# Sheet1.net
KiCad netlist of a schematic drawn in Altium Designer
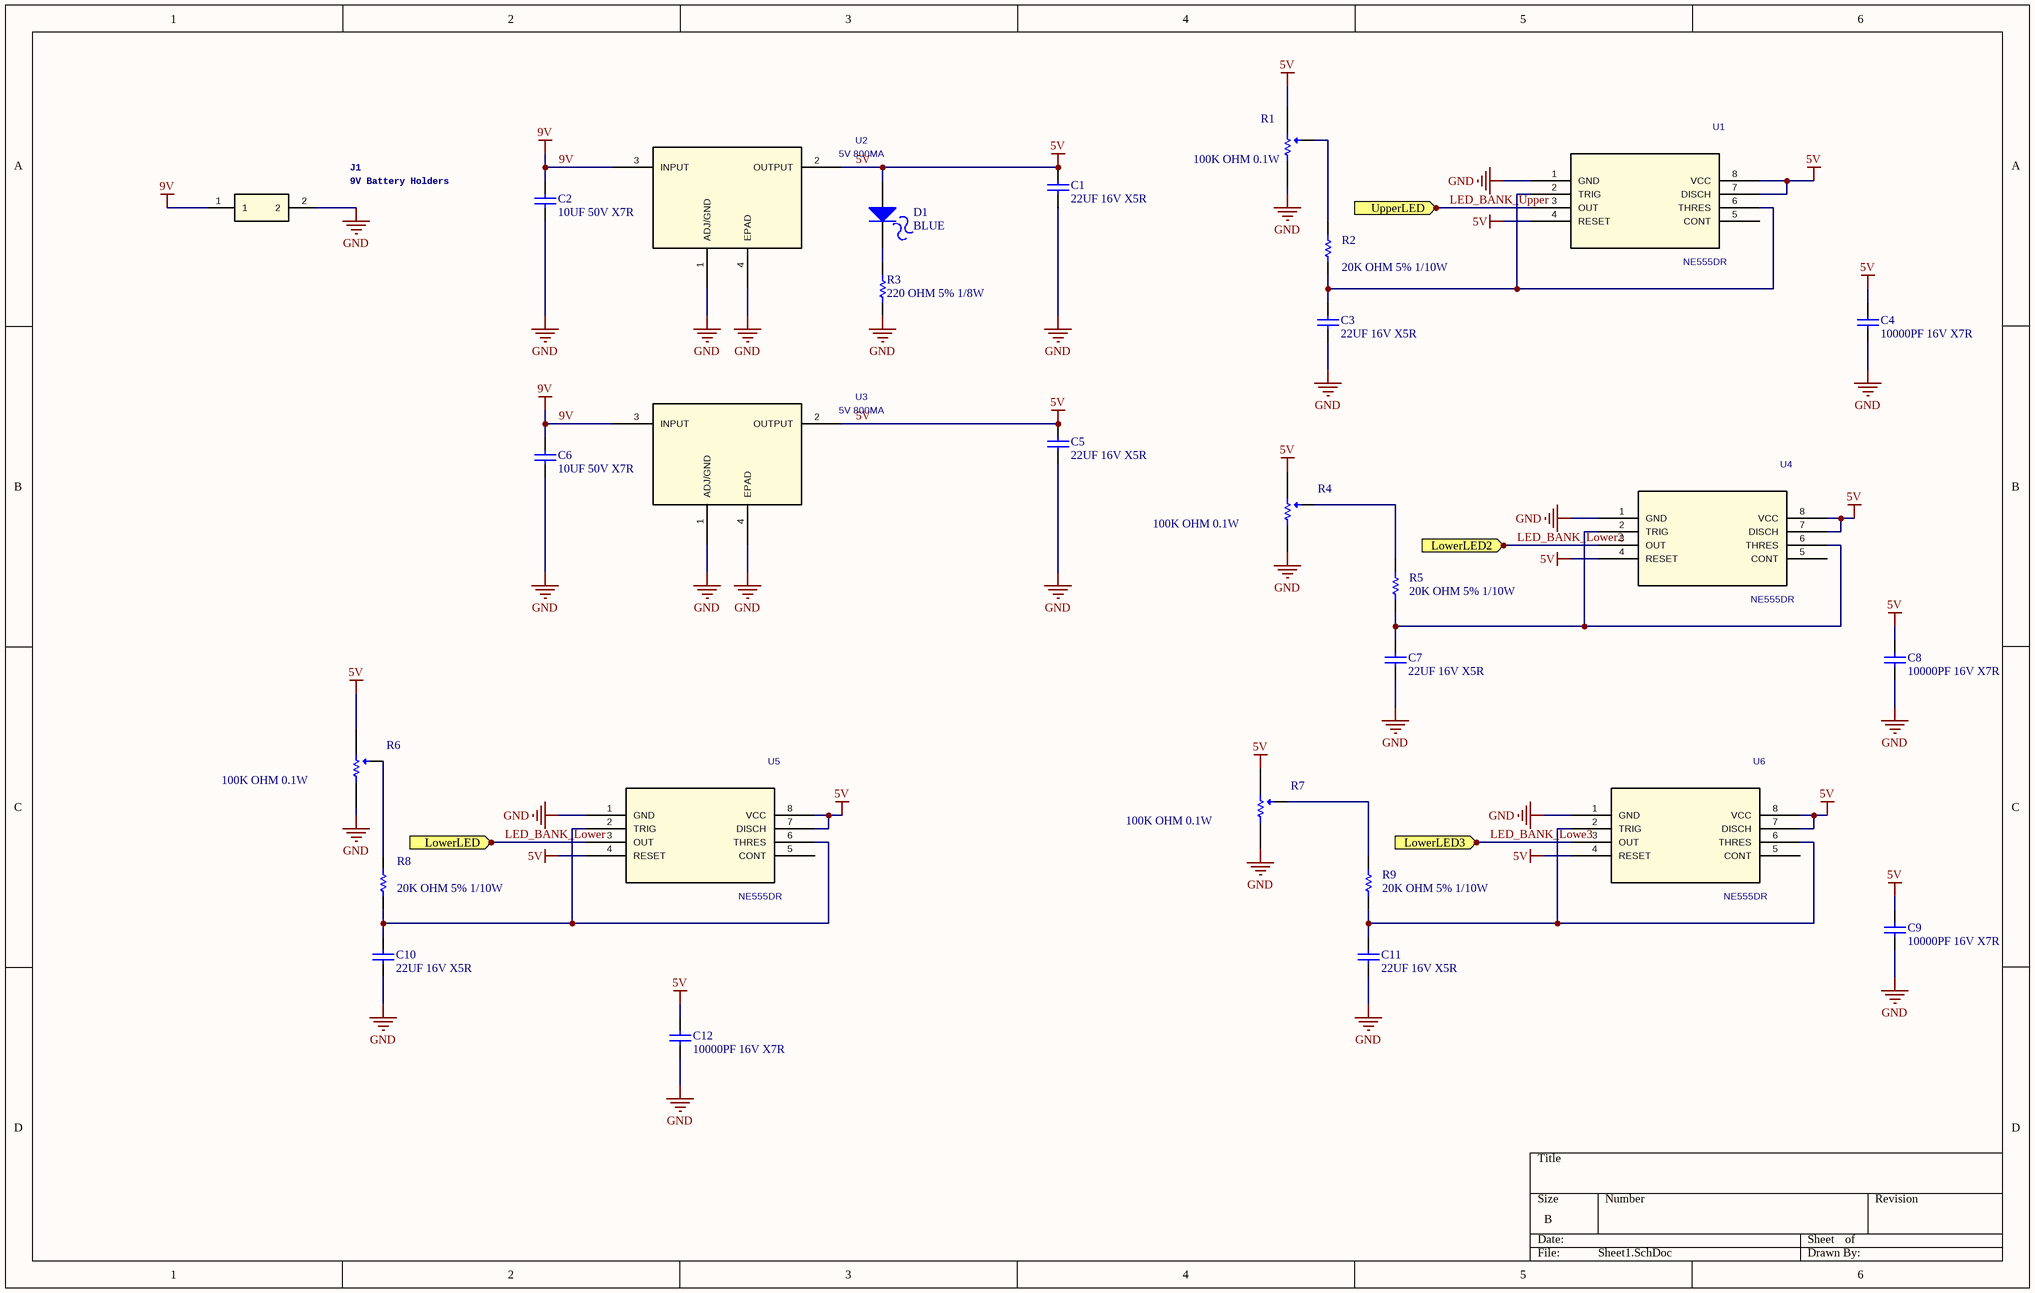
[diagram p0: Sheet1.SchDoc]

(export (version "E")
  (design (tool "Eeschema 10.0.6"))
  (components
    (comp (ref "C1")
      (value "22UF 16V X5R")
      (footprint "SMD-0805C")
      (description "CAP CER 22UF 16V X5R 0805")
      (fields (field (name "MANUFACTURER") "Samsung Electro-Mechanics"))
      (libsource (lib "CircuitStudioSchematic.Lib") (part "CL21A226MOCLRNC"))
    )
    (comp (ref "C2")
      (value "10UF 50V X7R")
      (footprint "2220 cap")
      (description "CAP CER 10UF 50V X7R 2220")
      (fields (field (name "MANUFACTURER") "TDK Corporation"))
      (libsource (lib "CircuitStudioSchematic.Lib") (part "CGA9N3X7R1H106K230KB"))
    )
    (comp (ref "C3")
      (value "22UF 16V X5R")
      (footprint "SMD-0805C")
      (description "CAP CER 22UF 16V X5R 0805")
      (fields (field (name "MANUFACTURER") "Samsung Electro-Mechanics"))
      (libsource (lib "CircuitStudioSchematic.Lib") (part "CL21A226MOCLRNC"))
    )
    (comp (ref "C4")
      (value "10000PF 16V X7R")
      (footprint "SMD-0603C")
      (description "CAP CER 10000PF 16V X7R 0603")
      (fields (field (name "MANUFACTURER") "KEMET"))
      (libsource (lib "CircuitStudioSchematic.Lib") (part "C0603C103K4RACTU"))
    )
    (comp (ref "C5")
      (value "22UF 16V X5R")
      (footprint "SMD-0805C")
      (description "CAP CER 22UF 16V X5R 0805")
      (fields (field (name "MANUFACTURER") "Samsung Electro-Mechanics"))
      (libsource (lib "CircuitStudioSchematic.Lib") (part "CL21A226MOCLRNC"))
    )
    (comp (ref "C6")
      (value "10UF 50V X7R")
      (footprint "2220 cap")
      (description "CAP CER 10UF 50V X7R 2220")
      (fields (field (name "MANUFACTURER") "TDK Corporation"))
      (libsource (lib "CircuitStudioSchematic.Lib") (part "CGA9N3X7R1H106K230KB"))
    )
    (comp (ref "C7")
      (value "22UF 16V X5R")
      (footprint "SMD-0805C")
      (description "CAP CER 22UF 16V X5R 0805")
      (fields (field (name "MANUFACTURER") "Samsung Electro-Mechanics"))
      (libsource (lib "CircuitStudioSchematic.Lib") (part "CL21A226MOCLRNC"))
    )
    (comp (ref "C8")
      (value "10000PF 16V X7R")
      (footprint "SMD-0603C")
      (description "CAP CER 10000PF 16V X7R 0603")
      (fields (field (name "MANUFACTURER") "KEMET"))
      (libsource (lib "CircuitStudioSchematic.Lib") (part "C0603C103K4RACTU"))
    )
    (comp (ref "C9")
      (value "10000PF 16V X7R")
      (footprint "SMD-0603C")
      (description "CAP CER 10000PF 16V X7R 0603")
      (fields (field (name "MANUFACTURER") "KEMET"))
      (libsource (lib "CircuitStudioSchematic.Lib") (part "C0603C103K4RACTU"))
    )
    (comp (ref "C10")
      (value "22UF 16V X5R")
      (footprint "SMD-0805C")
      (description "CAP CER 22UF 16V X5R 0805")
      (fields (field (name "MANUFACTURER") "Samsung Electro-Mechanics"))
      (libsource (lib "CircuitStudioSchematic.Lib") (part "CL21A226MOCLRNC"))
    )
    (comp (ref "C11")
      (value "22UF 16V X5R")
      (footprint "SMD-0805C")
      (description "CAP CER 22UF 16V X5R 0805")
      (fields (field (name "MANUFACTURER") "Samsung Electro-Mechanics"))
      (libsource (lib "CircuitStudioSchematic.Lib") (part "CL21A226MOCLRNC"))
    )
    (comp (ref "C12")
      (value "10000PF 16V X7R")
      (footprint "SMD-0603C")
      (description "CAP CER 10000PF 16V X7R 0603")
      (fields (field (name "MANUFACTURER") "KEMET"))
      (libsource (lib "CircuitStudioSchematic.Lib") (part "C0603C103K4RACTU"))
    )
    (comp (ref "D1")
      (value "BLUE")
      (footprint "0603 LED BLUE")
      (description "LED BLUE CLEAR CHIP SMD")
      (fields (field (name "MANUFACTURER") "Lite-On Inc."))
      (libsource (lib "CircuitStudioSchematic.Lib") (part "LTST-C190TBKT"))
    )
    (comp (ref "J1")
      (value "9V Battery Holders")
      (footprint "1294")
      (description "BATTERY HOLDER 9V PC PIN")
      (fields (field (name "MANUFACTURER") "Keystone Electronics"))
      (libsource (lib "CircuitStudioSchematic.Lib") (part "1294"))
    )
    (comp (ref "R1")
      (value "100K OHM 0.1W")
      (footprint "3.80mm x 3.60mm x 1.20mm POT")
      (description "TRIMMER 100K OHM 0.1W J LEAD TOP")
      (fields (field (name "MANUFACTURER") "TT Electronics/BI"))
      (libsource (lib "CircuitStudioSchematic.Lib") (part "TC33X-2-104E"))
    )
    (comp (ref "R2")
      (value "20K OHM 5% 1/10W")
      (footprint "SMD-0603-RES")
      (description "RES SMD 20K OHM 5% 1/10W 0603")
      (fields (field (name "MANUFACTURER") "Yageo"))
      (libsource (lib "CircuitStudioSchematic.Lib") (part "RC0603JR-0720KL"))
    )
    (comp (ref "R3")
      (value "220 OHM 5% 1/8W")
      (footprint "SMD-0805-RES")
      (description "RES SMD 220 OHM 5% 1/8W 0805")
      (fields (field (name "MANUFACTURER") "Yageo"))
      (libsource (lib "CircuitStudioSchematic.Lib") (part "RC0805JR-07220RL"))
    )
    (comp (ref "R4")
      (value "100K OHM 0.1W")
      (footprint "3.80mm x 3.60mm x 1.20mm POT")
      (description "TRIMMER 100K OHM 0.1W J LEAD TOP")
      (fields (field (name "MANUFACTURER") "TT Electronics/BI"))
      (libsource (lib "CircuitStudioSchematic.Lib") (part "TC33X-2-104E"))
    )
    (comp (ref "R5")
      (value "20K OHM 5% 1/10W")
      (footprint "SMD-0603-RES")
      (description "RES SMD 20K OHM 5% 1/10W 0603")
      (fields (field (name "MANUFACTURER") "Yageo"))
      (libsource (lib "CircuitStudioSchematic.Lib") (part "RC0603JR-0720KL"))
    )
    (comp (ref "R6")
      (value "100K OHM 0.1W")
      (footprint "3.80mm x 3.60mm x 1.20mm POT")
      (description "TRIMMER 100K OHM 0.1W J LEAD TOP")
      (fields (field (name "MANUFACTURER") "TT Electronics/BI"))
      (libsource (lib "CircuitStudioSchematic.Lib") (part "TC33X-2-104E"))
    )
    (comp (ref "R7")
      (value "100K OHM 0.1W")
      (footprint "3.80mm x 3.60mm x 1.20mm POT")
      (description "TRIMMER 100K OHM 0.1W J LEAD TOP")
      (fields (field (name "MANUFACTURER") "TT Electronics/BI"))
      (libsource (lib "CircuitStudioSchematic.Lib") (part "TC33X-2-104E"))
    )
    (comp (ref "R8")
      (value "20K OHM 5% 1/10W")
      (footprint "SMD-0603-RES")
      (description "RES SMD 20K OHM 5% 1/10W 0603")
      (fields (field (name "MANUFACTURER") "Yageo"))
      (libsource (lib "CircuitStudioSchematic.Lib") (part "RC0603JR-0720KL"))
    )
    (comp (ref "R9")
      (value "20K OHM 5% 1/10W")
      (footprint "SMD-0603-RES")
      (description "RES SMD 20K OHM 5% 1/10W 0603")
      (fields (field (name "MANUFACTURER") "Yageo"))
      (libsource (lib "CircuitStudioSchematic.Lib") (part "RC0603JR-0720KL"))
    )
    (comp (ref "U1")
      (value "NE555DR")
      (footprint "SOIC 8 TI")
      (description "IC OSC SGL TIMER 100KHZ 8-SOIC")
      (fields (field (name "MANUFACTURER") "Texas Instruments"))
      (libsource (lib "CircuitStudioSchematic.Lib") (part "NE555DR"))
    )
    (comp (ref "U2")
      (value "5V 800MA")
      (footprint "SOT-223")
      (description "IC REG LINEAR 5V 800MA SOT223")
      (fields (field (name "MANUFACTURER") "Diodes Incorporated"))
      (libsource (lib "CircuitStudioSchematic.Lib") (part "AZ1117CH-5.0TRG1"))
    )
    (comp (ref "U3")
      (value "5V 800MA")
      (footprint "SOT-223")
      (description "IC REG LINEAR 5V 800MA SOT223")
      (fields (field (name "MANUFACTURER") "Diodes Incorporated"))
      (libsource (lib "CircuitStudioSchematic.Lib") (part "AZ1117CH-5.0TRG1"))
    )
    (comp (ref "U4")
      (value "NE555DR")
      (footprint "SOIC 8 TI")
      (description "IC OSC SGL TIMER 100KHZ 8-SOIC")
      (fields (field (name "MANUFACTURER") "Texas Instruments"))
      (libsource (lib "CircuitStudioSchematic.Lib") (part "NE555DR"))
    )
    (comp (ref "U5")
      (value "NE555DR")
      (footprint "SOIC 8 TI")
      (description "IC OSC SGL TIMER 100KHZ 8-SOIC")
      (fields (field (name "MANUFACTURER") "Texas Instruments"))
      (libsource (lib "CircuitStudioSchematic.Lib") (part "NE555DR"))
    )
    (comp (ref "U6")
      (value "NE555DR")
      (footprint "SOIC 8 TI")
      (description "IC OSC SGL TIMER 100KHZ 8-SOIC")
      (fields (field (name "MANUFACTURER") "Texas Instruments"))
      (libsource (lib "CircuitStudioSchematic.Lib") (part "NE555DR"))
    )
  )
  (nets
    (net (code "1") (name "/LED_BANK_Lowe3") (class "Default")
      (node (ref "U6") (pin "3") (pinfunction "OUT_3") (pintype "passive"))
    )
    (net (code "2") (name "/LED_BANK_Lower") (class "Default")
      (node (ref "U5") (pin "3") (pinfunction "OUT_3") (pintype "passive"))
    )
    (net (code "3") (name "/LED_BANK_Lower2") (class "Default")
      (node (ref "U4") (pin "3") (pinfunction "OUT_3") (pintype "passive"))
    )
    (net (code "4") (name "/LED_BANK_Upper") (class "Default")
      (node (ref "U1") (pin "3") (pinfunction "OUT_3") (pintype "passive"))
    )
    (net (code "5") (name "5V") (class "Default")
      (node (ref "C1") (pin "2") (pinfunction "2_2") (pintype "passive"))
      (node (ref "C12") (pin "2") (pinfunction "2_2") (pintype "passive"))
      (node (ref "C4") (pin "2") (pinfunction "2_2") (pintype "passive"))
      (node (ref "C5") (pin "2") (pinfunction "2_2") (pintype "passive"))
      (node (ref "C8") (pin "2") (pinfunction "2_2") (pintype "passive"))
      (node (ref "C9") (pin "2") (pinfunction "2_2") (pintype "passive"))
      (node (ref "D1") (pin "1") (pinfunction "Anode_1") (pintype "passive"))
      (node (ref "R1") (pin "3") (pinfunction "3_3") (pintype "passive"))
      (node (ref "R4") (pin "3") (pinfunction "3_3") (pintype "passive"))
      (node (ref "R6") (pin "3") (pinfunction "3_3") (pintype "passive"))
      (node (ref "R7") (pin "3") (pinfunction "3_3") (pintype "passive"))
      (node (ref "U1") (pin "4") (pinfunction "RESET_4") (pintype "passive"))
      (node (ref "U1") (pin "7") (pinfunction "DISCH_7") (pintype "passive"))
      (node (ref "U1") (pin "8") (pinfunction "VCC_8") (pintype "power_in"))
      (node (ref "U2") (pin "2") (pinfunction "OUTPUT_2") (pintype "passive"))
      (node (ref "U3") (pin "2") (pinfunction "OUTPUT_2") (pintype "passive"))
      (node (ref "U4") (pin "4") (pinfunction "RESET_4") (pintype "passive"))
      (node (ref "U4") (pin "7") (pinfunction "DISCH_7") (pintype "passive"))
      (node (ref "U4") (pin "8") (pinfunction "VCC_8") (pintype "power_in"))
      (node (ref "U5") (pin "4") (pinfunction "RESET_4") (pintype "passive"))
      (node (ref "U5") (pin "7") (pinfunction "DISCH_7") (pintype "passive"))
      (node (ref "U5") (pin "8") (pinfunction "VCC_8") (pintype "power_in"))
      (node (ref "U6") (pin "4") (pinfunction "RESET_4") (pintype "passive"))
      (node (ref "U6") (pin "7") (pinfunction "DISCH_7") (pintype "passive"))
      (node (ref "U6") (pin "8") (pinfunction "VCC_8") (pintype "power_in"))
    )
    (net (code "6") (name "9V") (class "Default")
      (node (ref "C2") (pin "2") (pinfunction "2_2") (pintype "passive"))
      (node (ref "C6") (pin "2") (pinfunction "2_2") (pintype "passive"))
      (node (ref "J1") (pin "1") (pinfunction "1_1") (pintype "passive"))
      (node (ref "U2") (pin "3") (pinfunction "INPUT_3") (pintype "passive"))
      (node (ref "U3") (pin "3") (pinfunction "INPUT_3") (pintype "passive"))
    )
    (net (code "7") (name "GND") (class "Default")
      (node (ref "C1") (pin "1") (pinfunction "1_1") (pintype "passive"))
      (node (ref "C10") (pin "1") (pinfunction "1_1") (pintype "passive"))
      (node (ref "C11") (pin "1") (pinfunction "1_1") (pintype "passive"))
      (node (ref "C12") (pin "1") (pinfunction "1_1") (pintype "passive"))
      (node (ref "C2") (pin "1") (pinfunction "1_1") (pintype "passive"))
      (node (ref "C3") (pin "1") (pinfunction "1_1") (pintype "passive"))
      (node (ref "C4") (pin "1") (pinfunction "1_1") (pintype "passive"))
      (node (ref "C5") (pin "1") (pinfunction "1_1") (pintype "passive"))
      (node (ref "C6") (pin "1") (pinfunction "1_1") (pintype "passive"))
      (node (ref "C7") (pin "1") (pinfunction "1_1") (pintype "passive"))
      (node (ref "C8") (pin "1") (pinfunction "1_1") (pintype "passive"))
      (node (ref "C9") (pin "1") (pinfunction "1_1") (pintype "passive"))
      (node (ref "J1") (pin "2") (pinfunction "2_2") (pintype "passive"))
      (node (ref "R1") (pin "1") (pinfunction "1_1") (pintype "passive"))
      (node (ref "R3") (pin "1") (pinfunction "1_1") (pintype "passive"))
      (node (ref "R4") (pin "1") (pinfunction "1_1") (pintype "passive"))
      (node (ref "R6") (pin "1") (pinfunction "1_1") (pintype "passive"))
      (node (ref "R7") (pin "1") (pinfunction "1_1") (pintype "passive"))
      (node (ref "U1") (pin "1") (pinfunction "GND_1") (pintype "power_in"))
      (node (ref "U2") (pin "1") (pinfunction "ADJ/GND_1") (pintype "passive"))
      (node (ref "U2") (pin "4") (pinfunction "EPAD_4") (pintype "passive"))
      (node (ref "U3") (pin "1") (pinfunction "ADJ/GND_1") (pintype "passive"))
      (node (ref "U3") (pin "4") (pinfunction "EPAD_4") (pintype "passive"))
      (node (ref "U4") (pin "1") (pinfunction "GND_1") (pintype "power_in"))
      (node (ref "U5") (pin "1") (pinfunction "GND_1") (pintype "power_in"))
      (node (ref "U6") (pin "1") (pinfunction "GND_1") (pintype "power_in"))
    )
    (net (code "8") (name "Net-(D1-Cathode)") (class "Default")
      (node (ref "D1") (pin "2") (pinfunction "Cathode_2") (pintype "passive"))
      (node (ref "R3") (pin "2") (pinfunction "2_2") (pintype "passive"))
    )
    (net (code "9") (name "Net-(R1-Pad2)") (class "Default")
      (node (ref "R1") (pin "2") (pinfunction "2_2") (pintype "passive"))
      (node (ref "R2") (pin "2") (pinfunction "2_2") (pintype "passive"))
    )
    (net (code "10") (name "Net-(R4-Pad2)") (class "Default")
      (node (ref "R4") (pin "2") (pinfunction "2_2") (pintype "passive"))
      (node (ref "R5") (pin "2") (pinfunction "2_2") (pintype "passive"))
    )
    (net (code "11") (name "Net-(R6-Pad2)") (class "Default")
      (node (ref "R6") (pin "2") (pinfunction "2_2") (pintype "passive"))
      (node (ref "R8") (pin "2") (pinfunction "2_2") (pintype "passive"))
    )
    (net (code "12") (name "Net-(R7-Pad2)") (class "Default")
      (node (ref "R7") (pin "2") (pinfunction "2_2") (pintype "passive"))
      (node (ref "R9") (pin "2") (pinfunction "2_2") (pintype "passive"))
    )
    (net (code "13") (name "Net-(U1-THRES)") (class "Default")
      (node (ref "C3") (pin "2") (pinfunction "2_2") (pintype "passive"))
      (node (ref "R2") (pin "1") (pinfunction "1_1") (pintype "passive"))
      (node (ref "U1") (pin "2") (pinfunction "TRIG_2") (pintype "passive"))
      (node (ref "U1") (pin "6") (pinfunction "THRES_6") (pintype "passive"))
    )
    (net (code "14") (name "Net-(U4-THRES)") (class "Default")
      (node (ref "C7") (pin "2") (pinfunction "2_2") (pintype "passive"))
      (node (ref "R5") (pin "1") (pinfunction "1_1") (pintype "passive"))
      (node (ref "U4") (pin "2") (pinfunction "TRIG_2") (pintype "passive"))
      (node (ref "U4") (pin "6") (pinfunction "THRES_6") (pintype "passive"))
    )
    (net (code "15") (name "Net-(U5-THRES)") (class "Default")
      (node (ref "C10") (pin "2") (pinfunction "2_2") (pintype "passive"))
      (node (ref "R8") (pin "1") (pinfunction "1_1") (pintype "passive"))
      (node (ref "U5") (pin "2") (pinfunction "TRIG_2") (pintype "passive"))
      (node (ref "U5") (pin "6") (pinfunction "THRES_6") (pintype "passive"))
    )
    (net (code "16") (name "Net-(U6-THRES)") (class "Default")
      (node (ref "C11") (pin "2") (pinfunction "2_2") (pintype "passive"))
      (node (ref "R9") (pin "1") (pinfunction "1_1") (pintype "passive"))
      (node (ref "U6") (pin "2") (pinfunction "TRIG_2") (pintype "passive"))
      (node (ref "U6") (pin "6") (pinfunction "THRES_6") (pintype "passive"))
    )
    (net (code "17") (name "unconnected-(U1-CONT-Pad5)") (class "Default")
      (node (ref "U1") (pin "5") (pinfunction "CONT_5") (pintype "passive"))
    )
    (net (code "18") (name "unconnected-(U4-CONT-Pad5)") (class "Default")
      (node (ref "U4") (pin "5") (pinfunction "CONT_5") (pintype "passive"))
    )
    (net (code "19") (name "unconnected-(U5-CONT-Pad5)") (class "Default")
      (node (ref "U5") (pin "5") (pinfunction "CONT_5") (pintype "passive"))
    )
    (net (code "20") (name "unconnected-(U6-CONT-Pad5)") (class "Default")
      (node (ref "U6") (pin "5") (pinfunction "CONT_5") (pintype "passive"))
    )
  )
)
